# OpenROV_Topside_Interface_2_6.net
KiCad netlist of a schematic drawn in EAGLE
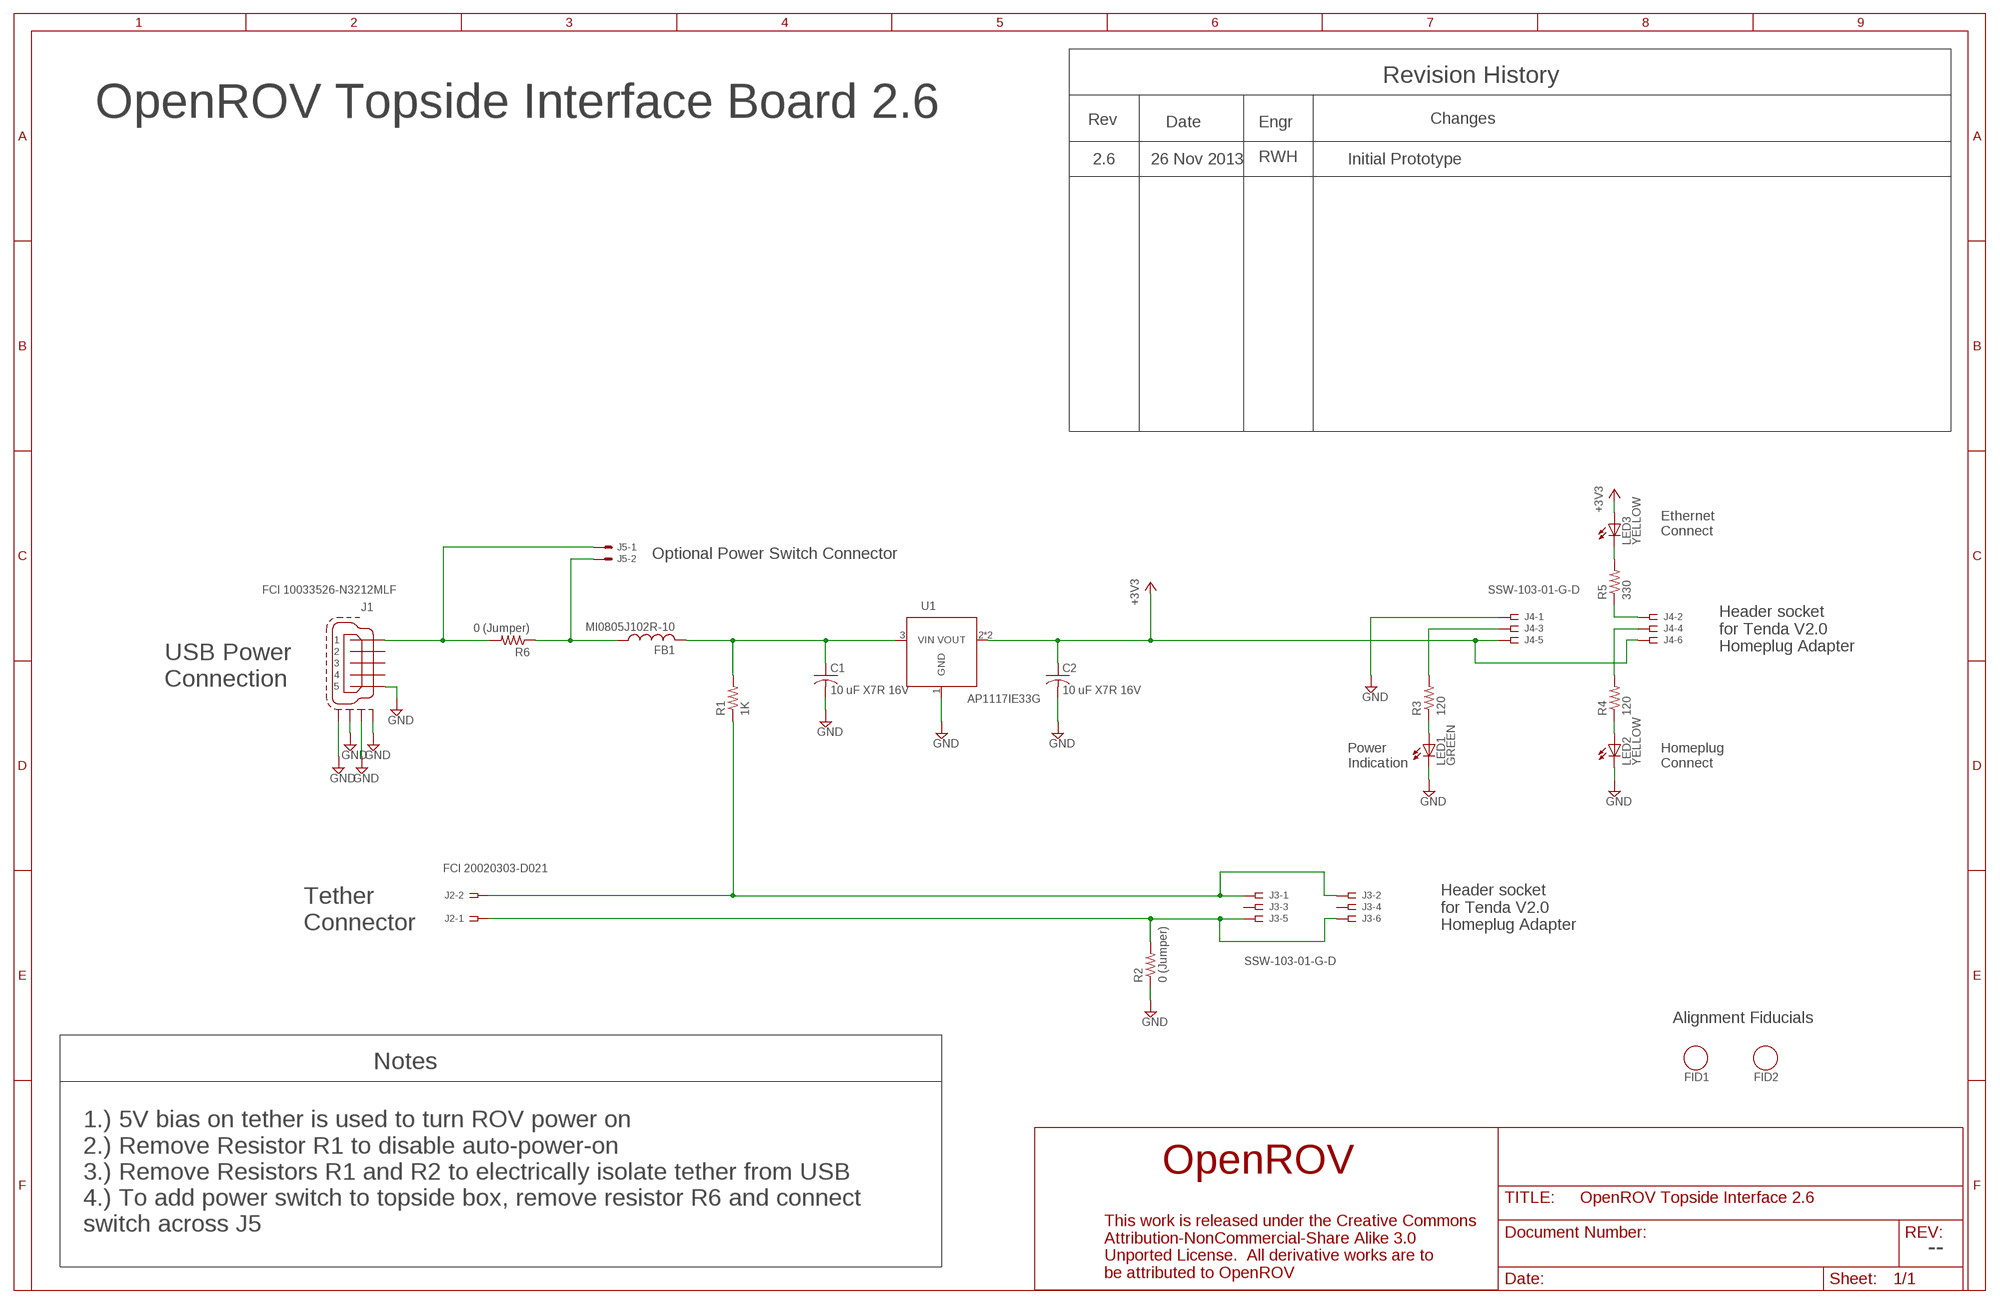
[diagram p0: schematic, sheet 1]

(export (version "E")
  (design (tool "Eeschema 10.0.6"))
  (components
    (comp (ref "C1")
      (value "10 uF X7R 16V")
      (footprint "eagle-import:R1206")
      (libsource (lib "eagle-import") (part "CAP1206"))
    )
    (comp (ref "C2")
      (value "10 uF X7R 16V")
      (footprint "eagle-import:R1206")
      (libsource (lib "eagle-import") (part "CAP1206"))
    )
    (comp (ref "FB1")
      (value "MI0805J102R-10")
      (footprint "eagle-import:R0805")
      (libsource (lib "eagle-import") (part "FERRITESIZE_0805"))
    )
    (comp (ref "FID1")
      (value "FIDUCIAL_1")
      (footprint "eagle-import:FIDUCIAL_1")
      (libsource (lib "eagle-import") (part "FIDUCIAL_1"))
    )
    (comp (ref "FID2")
      (value "FIDUCIAL_1")
      (footprint "eagle-import:FIDUCIAL_1")
      (libsource (lib "eagle-import") (part "FIDUCIAL_1"))
    )
    (comp (ref "J1")
      (value "FCI 10033526-N3212MLF")
      (footprint "eagle-import:USB_MINI-B_SM")
      (libsource (lib "eagle-import") (part "USB_MINI-BSURFACE_MOUNT"))
    )
    (comp (ref "J2")
      (value "FCI 20020303-D021")
      (footprint "eagle-import:FCI_09-381_2PL")
      (libsource (lib "eagle-import") (part "FCI_TERMINAL_BLOCK_2PL"))
    )
    (comp (ref "J3")
      (value "SSW-103-01-G-D")
      (footprint "eagle-import:SSW-103-02-S-D")
      (fields (field (name "MPN") "SSW-103-02-S-D"))
      (libsource (lib "eagle-import") (part "HDR_SOCKET_2X3"))
    )
    (comp (ref "J4")
      (value "SSW-103-01-G-D")
      (footprint "eagle-import:SSW-103-02-S-D")
      (fields (field (name "MPN") "SSW-103-02-S-D"))
      (libsource (lib "eagle-import") (part "HDR_SOCKET_2X3"))
    )
    (comp (ref "J5")
      (value "HDR_1X2X0.100-ALT_SILK")
      (footprint "eagle-import:22-23-2021_ALT_SILK")
      (libsource (lib "eagle-import") (part "HDR_1X2X0.100-ALT_SILK"))
    )
    (comp (ref "LED1")
      (value "GREEN")
      (footprint "eagle-import:LED_0805_BOTTOM_MT(OSRAM)")
      (libsource (lib "eagle-import") (part "LED-0805_BOTTOM_MT"))
    )
    (comp (ref "LED2")
      (value "YELLOW")
      (footprint "eagle-import:LED_0805_BOTTOM_MT(OSRAM)")
      (libsource (lib "eagle-import") (part "LED-0805_BOTTOM_MT"))
    )
    (comp (ref "LED3")
      (value "YELLOW")
      (footprint "eagle-import:LED_0805_BOTTOM_MT(OSRAM)")
      (libsource (lib "eagle-import") (part "LED-0805_BOTTOM_MT"))
    )
    (comp (ref "R1")
      (value "1K")
      (footprint "eagle-import:R0805")
      (libsource (lib "eagle-import") (part "RESISTOR-0805"))
    )
    (comp (ref "R2")
      (value "0 (Jumper)")
      (footprint "eagle-import:R0805")
      (libsource (lib "eagle-import") (part "RESISTOR-0805"))
    )
    (comp (ref "R3")
      (value "120")
      (footprint "eagle-import:R0805")
      (libsource (lib "eagle-import") (part "RESISTOR-0805"))
    )
    (comp (ref "R4")
      (value "120")
      (footprint "eagle-import:R0805")
      (libsource (lib "eagle-import") (part "RESISTOR-0805"))
    )
    (comp (ref "R5")
      (value "330")
      (footprint "eagle-import:R0805")
      (libsource (lib "eagle-import") (part "RESISTOR-0805"))
    )
    (comp (ref "R6")
      (value "0 (Jumper)")
      (footprint "eagle-import:R0805")
      (libsource (lib "eagle-import") (part "RESISTOR-0805"))
    )
    (comp (ref "U1")
      (value "AP1117IE33G")
      (footprint "eagle-import:SOT223")
      (libsource (lib "eagle-import") (part "AP1117SOT223"))
    )
  )
  (nets
    (net (code "1") (name "+3V3") (class "Default")
      (node (ref "C2") (pin "1") (pinfunction "1_1") (pintype "passive"))
      (node (ref "J4") (pin "5") (pinfunction "1_5") (pintype "passive"))
      (node (ref "J4") (pin "6") (pinfunction "1_6") (pintype "passive"))
      (node (ref "LED3") (pin "A") (pinfunction "A_A") (pintype "passive"))
      (node (ref "U1") (pin "2") (pinfunction "VOUT_2") (pintype "bidirectional"))
      (node (ref "U1") (pin "4") (pinfunction "VOUT_4") (pintype "bidirectional"))
    )
    (net (code "2") (name "GND") (class "Default")
      (node (ref "C1") (pin "2") (pinfunction "2_2") (pintype "passive"))
      (node (ref "C2") (pin "2") (pinfunction "2_2") (pintype "passive"))
      (node (ref "J1") (pin "5") (pinfunction "5_5") (pintype "passive"))
      (node (ref "J1") (pin "M1") (pinfunction "S1_M1") (pintype "passive"))
      (node (ref "J1") (pin "M2") (pinfunction "S2_M2") (pintype "passive"))
      (node (ref "J1") (pin "M3") (pinfunction "S3_M3") (pintype "passive"))
      (node (ref "J1") (pin "M4") (pinfunction "S4_M4") (pintype "passive"))
      (node (ref "J4") (pin "1") (pinfunction "1_1") (pintype "passive"))
      (node (ref "LED1") (pin "C") (pinfunction "C_C") (pintype "passive"))
      (node (ref "LED2") (pin "C") (pinfunction "C_C") (pintype "passive"))
      (node (ref "R2") (pin "1") (pinfunction "1_1") (pintype "passive"))
      (node (ref "U1") (pin "1") (pinfunction "GND_1") (pintype "power_in"))
    )
    (net (code "3") (name "Net-(J3B-1)") (class "Default")
      (node (ref "J2") (pin "2A") (pinfunction "1_2A") (pintype "passive"))
      (node (ref "J2") (pin "2B") (pinfunction "1_2B") (pintype "passive"))
      (node (ref "J3") (pin "1") (pinfunction "1_1") (pintype "passive"))
      (node (ref "J3") (pin "2") (pinfunction "1_2") (pintype "passive"))
      (node (ref "R1") (pin "1") (pinfunction "1_1") (pintype "passive"))
    )
    (net (code "4") (name "Net-(J3E-1)") (class "Default")
      (node (ref "J2") (pin "1A") (pinfunction "1_1A") (pintype "passive"))
      (node (ref "J2") (pin "1B") (pinfunction "1_1B") (pintype "passive"))
      (node (ref "J3") (pin "5") (pinfunction "1_5") (pintype "passive"))
      (node (ref "J3") (pin "6") (pinfunction "1_6") (pintype "passive"))
      (node (ref "R2") (pin "2") (pinfunction "2_2") (pintype "passive"))
    )
    (net (code "5") (name "Net-(J4B-1)") (class "Default")
      (node (ref "J4") (pin "2") (pinfunction "1_2") (pintype "passive"))
      (node (ref "R5") (pin "1") (pinfunction "1_1") (pintype "passive"))
    )
    (net (code "6") (name "Net-(J4C-1)") (class "Default")
      (node (ref "J4") (pin "3") (pinfunction "1_3") (pintype "passive"))
      (node (ref "R3") (pin "2") (pinfunction "2_2") (pintype "passive"))
    )
    (net (code "7") (name "Net-(J4D-1)") (class "Default")
      (node (ref "J4") (pin "4") (pinfunction "1_4") (pintype "passive"))
      (node (ref "R4") (pin "2") (pinfunction "2_2") (pintype "passive"))
    )
    (net (code "8") (name "Net-(J5A-S)") (class "Default")
      (node (ref "J1") (pin "1") (pinfunction "1_1") (pintype "passive"))
      (node (ref "J5") (pin "1") (pinfunction "S_1") (pintype "passive"))
      (node (ref "R6") (pin "2") (pinfunction "2_2") (pintype "passive"))
    )
    (net (code "9") (name "Net-(J5B-S)") (class "Default")
      (node (ref "FB1") (pin "1") (pinfunction "1_1") (pintype "passive"))
      (node (ref "J5") (pin "2") (pinfunction "S_2") (pintype "passive"))
      (node (ref "R6") (pin "1") (pinfunction "1_1") (pintype "passive"))
    )
    (net (code "10") (name "Net-(LED1-PadA)") (class "Default")
      (node (ref "LED1") (pin "A") (pinfunction "A_A") (pintype "passive"))
      (node (ref "R3") (pin "1") (pinfunction "1_1") (pintype "passive"))
    )
    (net (code "11") (name "Net-(LED2-PadA)") (class "Default")
      (node (ref "LED2") (pin "A") (pinfunction "A_A") (pintype "passive"))
      (node (ref "R4") (pin "1") (pinfunction "1_1") (pintype "passive"))
    )
    (net (code "12") (name "Net-(LED3-PadC)") (class "Default")
      (node (ref "LED3") (pin "C") (pinfunction "C_C") (pintype "passive"))
      (node (ref "R5") (pin "2") (pinfunction "2_2") (pintype "passive"))
    )
    (net (code "13") (name "Net-(U1-VIN)") (class "Default")
      (node (ref "C1") (pin "1") (pinfunction "1_1") (pintype "passive"))
      (node (ref "FB1") (pin "2") (pinfunction "2_2") (pintype "passive"))
      (node (ref "R1") (pin "2") (pinfunction "2_2") (pintype "passive"))
      (node (ref "U1") (pin "3") (pinfunction "VIN_3") (pintype "input"))
    )
    (net (code "14") (name "unconnected-(J1-Pad2)") (class "Default")
      (node (ref "J1") (pin "2") (pinfunction "2_2") (pintype "passive"))
    )
    (net (code "15") (name "unconnected-(J1-Pad3)") (class "Default")
      (node (ref "J1") (pin "3") (pinfunction "3_3") (pintype "passive"))
    )
    (net (code "16") (name "unconnected-(J1-Pad4)") (class "Default")
      (node (ref "J1") (pin "4") (pinfunction "4_4") (pintype "passive"))
    )
    (net (code "17") (name "unconnected-(J3C-1-Pad3)") (class "Default")
      (node (ref "J3") (pin "3") (pinfunction "1_3") (pintype "passive"))
    )
    (net (code "18") (name "unconnected-(J3D-1-Pad4)") (class "Default")
      (node (ref "J3") (pin "4") (pinfunction "1_4") (pintype "passive"))
    )
  )
)
